# PWM_Regulator.net
KiCad netlist of a schematic drawn in EAGLE
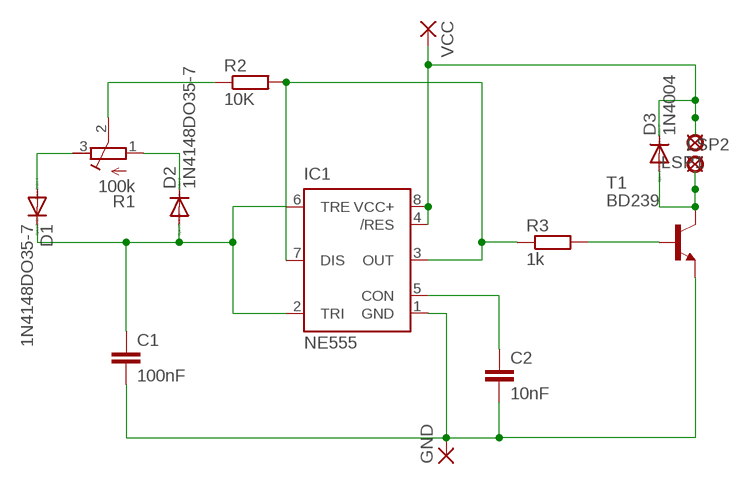
[diagram p0: schematic, sheet 1]

(export (version "E")
  (design (tool "Eeschema 10.0.6"))
  (components
    (comp (ref "C1")
      (value "100nF")
      (footprint "eagle-import:C050-024X044")
      (libsource (lib "eagle-import") (part "C-EU050-024X044"))
    )
    (comp (ref "C2")
      (value "10nF")
      (footprint "eagle-import:C050-024X044")
      (libsource (lib "eagle-import") (part "C-EU050-024X044"))
    )
    (comp (ref "D1")
      (value "1N4148DO35-7")
      (footprint "eagle-import:DO35-7")
      (libsource (lib "eagle-import") (part "1N4148DO35-7"))
    )
    (comp (ref "D2")
      (value "1N4148DO35-7")
      (footprint "eagle-import:DO35-7")
      (libsource (lib "eagle-import") (part "1N4148DO35-7"))
    )
    (comp (ref "D3")
      (value "1N4004")
      (footprint "eagle-import:DO41-10")
      (libsource (lib "eagle-import") (part "1N4004"))
    )
    (comp (ref "GND")
      (value "2,54/0,8")
      (footprint "eagle-import:2,54_0,8")
      (libsource (lib "eagle-import") (part "2,54/0,8"))
    )
    (comp (ref "IC1")
      (value "NE555")
      (footprint "eagle-import:DIL-08")
      (fields (field (name "MF") "Arrow Electronics") (field (name "MPN") "NE555N"))
      (libsource (lib "eagle-import") (part "NE555"))
    )
    (comp (ref "LSP1")
      (value "LSP10")
      (footprint "eagle-import:LSP10")
      (libsource (lib "eagle-import") (part "LSP10"))
    )
    (comp (ref "LSP2")
      (value "LSP10")
      (footprint "eagle-import:LSP10")
      (libsource (lib "eagle-import") (part "LSP10"))
    )
    (comp (ref "R1")
      (value "100k")
      (footprint "eagle-import:RTRIM3339P")
      (libsource (lib "eagle-import") (part "R-TRIMM3339P"))
    )
    (comp (ref "R2")
      (value "10K")
      (footprint "eagle-import:0204_7")
      (libsource (lib "eagle-import") (part "R-EU_0204/7"))
    )
    (comp (ref "R3")
      (value "1k")
      (footprint "eagle-import:0207_10")
      (libsource (lib "eagle-import") (part "R-EU_0207/10"))
    )
    (comp (ref "T1")
      (value "BD239")
      (footprint "eagle-import:TO220")
      (libsource (lib "eagle-import") (part "BD239"))
    )
    (comp (ref "VCC")
      (value "2,54/0,8")
      (footprint "eagle-import:2,54_0,8")
      (libsource (lib "eagle-import") (part "2,54/0,8"))
    )
  )
  (nets
    (net (code "1") (name "Net-(GND-P)") (class "Default")
      (node (ref "C1") (pin "2") (pinfunction "2_2") (pintype "passive"))
      (node (ref "C2") (pin "2") (pinfunction "2_2") (pintype "passive"))
      (node (ref "GND") (pin "1") (pinfunction "P_1") (pintype "passive"))
      (node (ref "IC1") (pin "1") (pinfunction "GND_1") (pintype "power_in"))
      (node (ref "T1") (pin "3") (pinfunction "E_3") (pintype "passive"))
    )
    (net (code "2") (name "Net-(IC1-CON)") (class "Default")
      (node (ref "C2") (pin "1") (pinfunction "1_1") (pintype "passive"))
      (node (ref "IC1") (pin "5") (pinfunction "CON_5") (pintype "input"))
    )
    (net (code "3") (name "Net-(IC1-DIS)") (class "Default")
      (node (ref "IC1") (pin "3") (pinfunction "OUT_3") (pintype "output"))
      (node (ref "IC1") (pin "7") (pinfunction "DIS_7") (pintype "input"))
      (node (ref "R2") (pin "2") (pinfunction "2_2") (pintype "passive"))
      (node (ref "R3") (pin "1") (pinfunction "1_1") (pintype "passive"))
    )
    (net (code "4") (name "Net-(IC1-TRE)") (class "Default")
      (node (ref "C1") (pin "1") (pinfunction "1_1") (pintype "passive"))
      (node (ref "D1") (pin "C") (pinfunction "C_C") (pintype "passive"))
      (node (ref "D2") (pin "A") (pinfunction "A_A") (pintype "passive"))
      (node (ref "IC1") (pin "2") (pinfunction "TRI_2") (pintype "input"))
      (node (ref "IC1") (pin "6") (pinfunction "TRE_6") (pintype "input"))
    )
    (net (code "5") (name "Net-(IC1-VCC+)") (class "Default")
      (node (ref "D3") (pin "C") (pinfunction "C_C") (pintype "passive"))
      (node (ref "IC1") (pin "4") (pinfunction "/RES_4") (pintype "input"))
      (node (ref "IC1") (pin "8") (pinfunction "VCC+_8") (pintype "power_in"))
      (node (ref "LSP1") (pin "MP") (pinfunction "MP_MP") (pintype "passive"))
      (node (ref "VCC") (pin "1") (pinfunction "P_1") (pintype "passive"))
    )
    (net (code "6") (name "Net-(R1-A)") (class "Default")
      (node (ref "D2") (pin "C") (pinfunction "C_C") (pintype "passive"))
      (node (ref "R1") (pin "1") (pinfunction "A_1") (pintype "passive"))
    )
    (net (code "7") (name "Net-(R1-E)") (class "Default")
      (node (ref "D1") (pin "A") (pinfunction "A_A") (pintype "passive"))
      (node (ref "R1") (pin "3") (pinfunction "E_3") (pintype "passive"))
    )
    (net (code "8") (name "Net-(R1-S)") (class "Default")
      (node (ref "R1") (pin "2") (pinfunction "S_2") (pintype "passive"))
      (node (ref "R2") (pin "1") (pinfunction "1_1") (pintype "passive"))
    )
    (net (code "9") (name "Net-(T1-B)") (class "Default")
      (node (ref "R3") (pin "2") (pinfunction "2_2") (pintype "passive"))
      (node (ref "T1") (pin "1") (pinfunction "B_1") (pintype "passive"))
    )
    (net (code "10") (name "Net-(T1-C)") (class "Default")
      (node (ref "D3") (pin "A") (pinfunction "A_A") (pintype "passive"))
      (node (ref "LSP2") (pin "MP") (pinfunction "MP_MP") (pintype "passive"))
      (node (ref "T1") (pin "2") (pinfunction "C_2") (pintype "passive"))
    )
  )
)
